# ESP32_EVKIT_v1_0.net
KiCad netlist of a schematic drawn in EAGLE
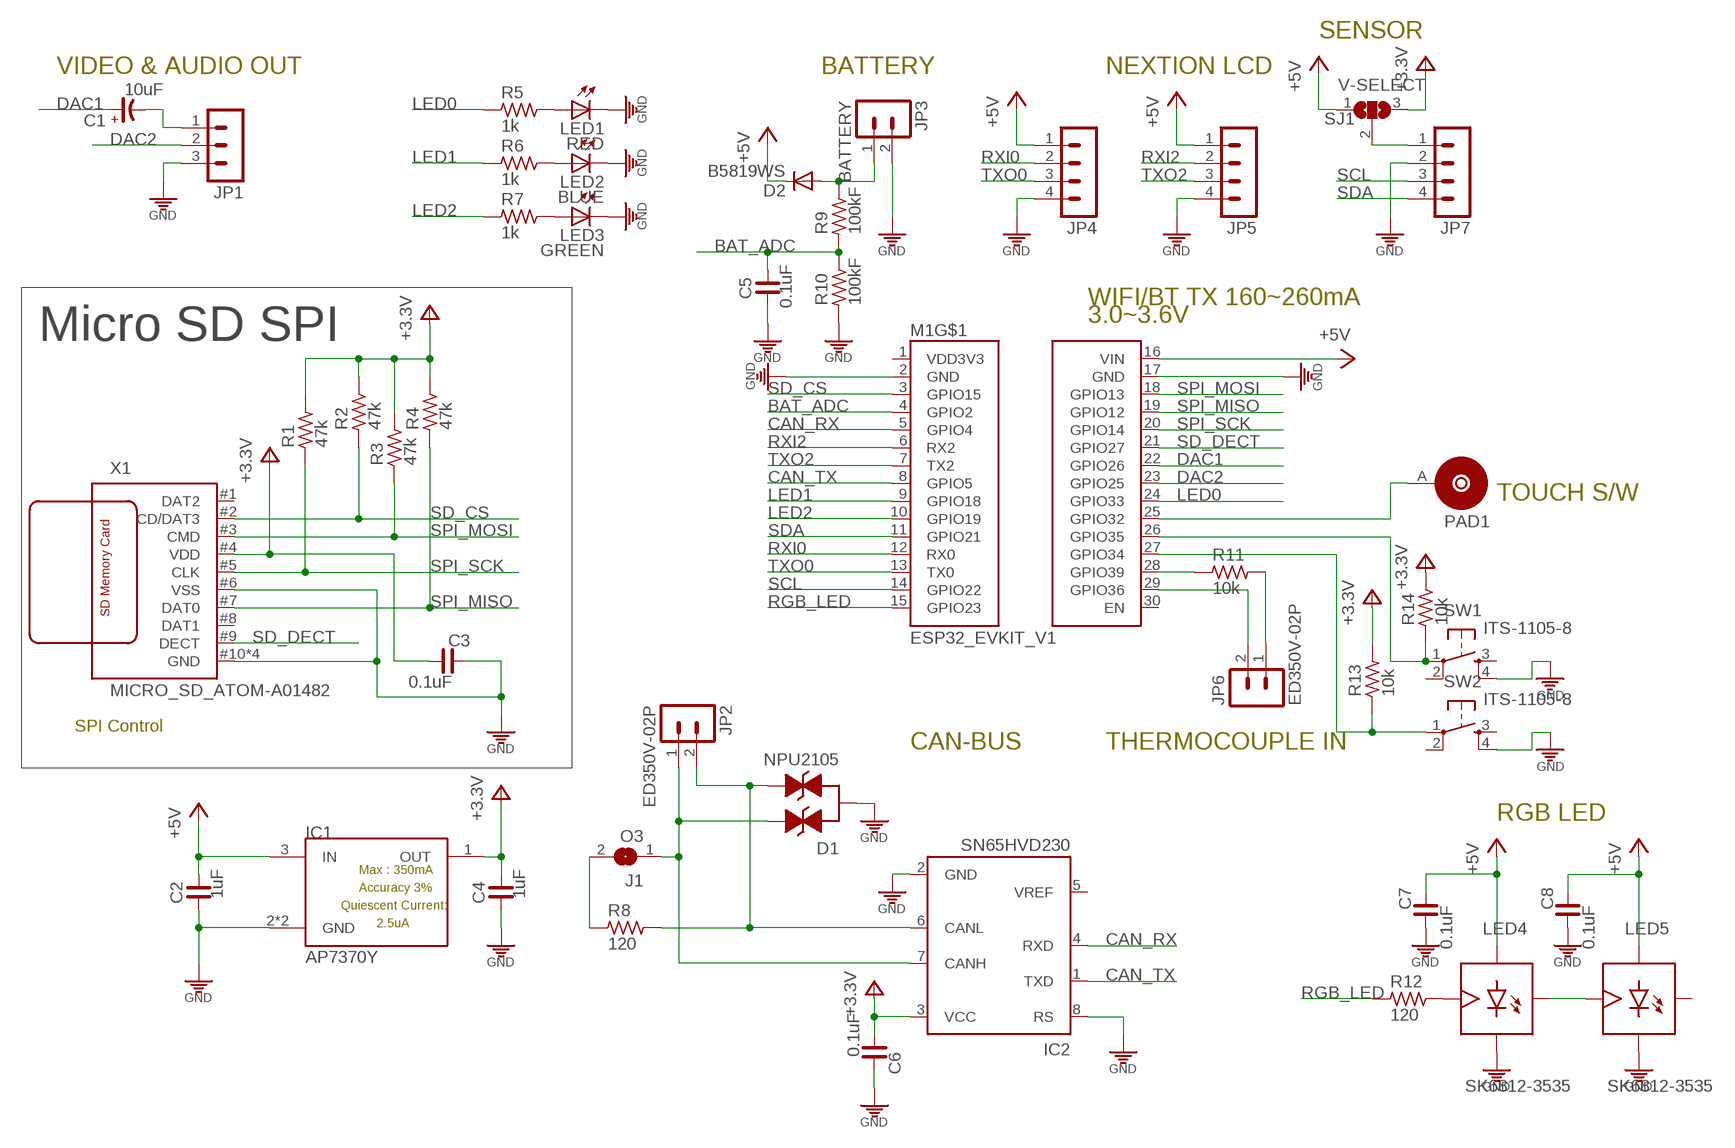
[diagram p0: schematic, sheet 1]

(export (version "E")
  (design (tool "Eeschema 10.0.6"))
  (components
    (comp (ref "C1")
      (value "10uF")
      (footprint "eagle-import:C2012_T")
      (libsource (lib "eagle-import") (part "CP_2012"))
    )
    (comp (ref "C2")
      (value "1uF")
      (footprint "eagle-import:C0603")
      (libsource (lib "eagle-import") (part "C_0603"))
    )
    (comp (ref "C3")
      (value "0.1uF")
      (footprint "eagle-import:C0603")
      (libsource (lib "eagle-import") (part "C_0603"))
    )
    (comp (ref "C4")
      (value "1uF")
      (footprint "eagle-import:C0603")
      (libsource (lib "eagle-import") (part "C_0603"))
    )
    (comp (ref "C5")
      (value "0.1uF")
      (footprint "eagle-import:C0603")
      (libsource (lib "eagle-import") (part "C_0603"))
    )
    (comp (ref "C6")
      (value "0.1uF")
      (footprint "eagle-import:C0603")
      (libsource (lib "eagle-import") (part "C_0603"))
    )
    (comp (ref "C7")
      (value "0.1uF")
      (footprint "eagle-import:C0603")
      (libsource (lib "eagle-import") (part "C_0603"))
    )
    (comp (ref "C8")
      (value "0.1uF")
      (footprint "eagle-import:C0603")
      (libsource (lib "eagle-import") (part "C_0603"))
    )
    (comp (ref "D1")
      (value "NPU2105")
      (footprint "eagle-import:SOT23@2")
      (libsource (lib "eagle-import") (part "NPU2105"))
    )
    (comp (ref "D2")
      (value "B5819WS")
      (footprint "eagle-import:SOD323-W")
      (libsource (lib "eagle-import") (part "B5189WWS"))
    )
    (comp (ref "IC1")
      (value "AP7370Y")
      (footprint "eagle-import:SOT89")
      (libsource (lib "eagle-import") (part "AP7370Y"))
    )
    (comp (ref "IC2")
      (value "SN65HVD230")
      (footprint "eagle-import:SO8")
      (libsource (lib "eagle-import") (part "PCA82C250T"))
    )
    (comp (ref "J1") (value "O3") (footprint "eagle-import:SJ") (libsource (lib "eagle-import") (part "SJ")))
    (comp (ref "JP1")
      (value "MA03-1DEF")
      (footprint "eagle-import:MA03")
      (libsource (lib "eagle-import") (part "MA03-1DEF"))
    )
    (comp (ref "JP2")
      (value "ED350V-02P")
      (footprint "eagle-import:ED350V-02P")
      (libsource (lib "eagle-import") (part "MA02ED350V-02P"))
    )
    (comp (ref "JP3")
      (value "BATTERY")
      (footprint "eagle-import:53398-02")
      (libsource (lib "eagle-import") (part "MA0253398"))
    )
    (comp (ref "JP4")
      (value "MA04-1SMALL")
      (footprint "eagle-import:MA04-1-S")
      (libsource (lib "eagle-import") (part "MA04-1SMALL"))
    )
    (comp (ref "JP5")
      (value "MA04-1SMALL")
      (footprint "eagle-import:MA04-1-S")
      (libsource (lib "eagle-import") (part "MA04-1SMALL"))
    )
    (comp (ref "JP6")
      (value "ED350V-02P")
      (footprint "eagle-import:ED350V-02P")
      (libsource (lib "eagle-import") (part "MA02ED350V-02P"))
    )
    (comp (ref "JP7")
      (value "MA04-1SMALL")
      (footprint "eagle-import:MA04-1-S")
      (libsource (lib "eagle-import") (part "MA04-1SMALL"))
    )
    (comp (ref "LED1")
      (value "RED")
      (footprint "eagle-import:LED-1608")
      (libsource (lib "eagle-import") (part "LEDSMD-1608"))
    )
    (comp (ref "LED2")
      (value "BLUE")
      (footprint "eagle-import:LED-1608")
      (libsource (lib "eagle-import") (part "LEDSMD-1608"))
    )
    (comp (ref "LED3")
      (value "GREEN")
      (footprint "eagle-import:LED-1608")
      (libsource (lib "eagle-import") (part "LEDSMD-1608"))
    )
    (comp (ref "LED4")
      (value "SK6812-3535")
      (footprint "eagle-import:LED3535")
      (libsource (lib "eagle-import") (part "SK68123535"))
    )
    (comp (ref "LED5")
      (value "SK6812-3535")
      (footprint "eagle-import:LED3535")
      (libsource (lib "eagle-import") (part "SK68123535"))
    )
    (comp (ref "M1")
      (value "ESP32_EVKIT_V1")
      (footprint "eagle-import:ESP32_DEVKIT_V1_DOIT")
      (libsource (lib "eagle-import") (part "ESP32_EVKIT_V1"))
    )
    (comp (ref "PAD1")
      (value "TOUCH_PAD01")
      (footprint "eagle-import:TOUCH_PAD1")
      (libsource (lib "eagle-import") (part "TOUCH_PAD01"))
    )
    (comp (ref "R1")
      (value "47k")
      (footprint "eagle-import:R0603")
      (libsource (lib "eagle-import") (part "R_0603"))
    )
    (comp (ref "R2")
      (value "47k")
      (footprint "eagle-import:R0603")
      (libsource (lib "eagle-import") (part "R_0603"))
    )
    (comp (ref "R3")
      (value "47k")
      (footprint "eagle-import:R0603")
      (libsource (lib "eagle-import") (part "R_0603"))
    )
    (comp (ref "R4")
      (value "47k")
      (footprint "eagle-import:R0603")
      (libsource (lib "eagle-import") (part "R_0603"))
    )
    (comp (ref "R5")
      (value "1k")
      (footprint "eagle-import:R0603")
      (libsource (lib "eagle-import") (part "R_0603"))
    )
    (comp (ref "R6")
      (value "1k")
      (footprint "eagle-import:R0603")
      (libsource (lib "eagle-import") (part "R_0603"))
    )
    (comp (ref "R7")
      (value "1k")
      (footprint "eagle-import:R0603")
      (libsource (lib "eagle-import") (part "R_0603"))
    )
    (comp (ref "R8")
      (value "120")
      (footprint "eagle-import:R0603")
      (libsource (lib "eagle-import") (part "R_0603"))
    )
    (comp (ref "R9")
      (value "100kF")
      (footprint "eagle-import:R0603")
      (libsource (lib "eagle-import") (part "R_0603"))
    )
    (comp (ref "R10")
      (value "100kF")
      (footprint "eagle-import:R0603")
      (libsource (lib "eagle-import") (part "R_0603"))
    )
    (comp (ref "R11")
      (value "10k")
      (footprint "eagle-import:R0603")
      (libsource (lib "eagle-import") (part "R_0603"))
    )
    (comp (ref "R12")
      (value "120")
      (footprint "eagle-import:R0603")
      (libsource (lib "eagle-import") (part "R_0603"))
    )
    (comp (ref "R13")
      (value "10k")
      (footprint "eagle-import:R0603")
      (libsource (lib "eagle-import") (part "R_0603"))
    )
    (comp (ref "R14")
      (value "10k")
      (footprint "eagle-import:R0603")
      (libsource (lib "eagle-import") (part "R_0603"))
    )
    (comp (ref "SJ1")
      (value "V-SELECT")
      (footprint "eagle-import:SJ_3")
      (libsource (lib "eagle-import") (part "SOLDERJUMPER_2WAYS"))
    )
    (comp (ref "SW1")
      (value "ITS-1105-8")
      (footprint "eagle-import:ITS-1105")
      (libsource (lib "eagle-import") (part "ITS-1105"))
    )
    (comp (ref "SW2")
      (value "ITS-1105-8")
      (footprint "eagle-import:ITS-1105")
      (libsource (lib "eagle-import") (part "ITS-1105"))
    )
    (comp (ref "X1")
      (value "MICRO_SD_ATOM-A01482")
      (footprint "eagle-import:ATOM-A01482")
      (libsource (lib "eagle-import") (part "MICRO_SD_ATOM-A01482"))
    )
  )
  (nets
    (net (code "1") (name "+3V3") (class "Default")
      (node (ref "C3") (pin "2") (pinfunction "2_2") (pintype "passive"))
      (node (ref "C4") (pin "1") (pinfunction "1_1") (pintype "passive"))
      (node (ref "C6") (pin "2") (pinfunction "2_2") (pintype "passive"))
      (node (ref "IC1") (pin "1") (pinfunction "OUT_1") (pintype "power_in"))
      (node (ref "IC2") (pin "3") (pinfunction "VCC_3") (pintype "power_in"))
      (node (ref "R1") (pin "2") (pinfunction "2_2") (pintype "passive"))
      (node (ref "R13") (pin "2") (pinfunction "2_2") (pintype "passive"))
      (node (ref "R14") (pin "2") (pinfunction "2_2") (pintype "passive"))
      (node (ref "R2") (pin "2") (pinfunction "2_2") (pintype "passive"))
      (node (ref "R3") (pin "2") (pinfunction "2_2") (pintype "passive"))
      (node (ref "R4") (pin "2") (pinfunction "2_2") (pintype "passive"))
      (node (ref "SJ1") (pin "3") (pinfunction "3_3") (pintype "passive"))
      (node (ref "X1") (pin "#4") (pinfunction "VDD_#4") (pintype "passive"))
    )
    (net (code "2") (name "+5V") (class "Default")
      (node (ref "C2") (pin "1") (pinfunction "1_1") (pintype "passive"))
      (node (ref "C7") (pin "1") (pinfunction "1_1") (pintype "passive"))
      (node (ref "C8") (pin "1") (pinfunction "1_1") (pintype "passive"))
      (node (ref "D2") (pin "C") (pinfunction "C_C") (pintype "passive"))
      (node (ref "IC1") (pin "3") (pinfunction "IN_3") (pintype "power_in"))
      (node (ref "JP4") (pin "1") (pinfunction "1_1") (pintype "passive"))
      (node (ref "JP5") (pin "1") (pinfunction "1_1") (pintype "passive"))
      (node (ref "LED4") (pin "4") (pinfunction "VDD_4") (pintype "power_in"))
      (node (ref "LED5") (pin "4") (pinfunction "VDD_4") (pintype "power_in"))
      (node (ref "M1") (pin "16") (pinfunction "VIN_16") (pintype "power_in"))
      (node (ref "SJ1") (pin "1") (pinfunction "1_1") (pintype "passive"))
    )
    (net (code "3") (name "/BAT_ADC") (class "Default")
      (node (ref "C5") (pin "1") (pinfunction "1_1") (pintype "passive"))
      (node (ref "M1") (pin "4") (pinfunction "GPIO2_4") (pintype "bidirectional"))
      (node (ref "R10") (pin "2") (pinfunction "2_2") (pintype "passive"))
      (node (ref "R9") (pin "1") (pinfunction "1_1") (pintype "passive"))
    )
    (net (code "4") (name "/CAN_RX") (class "Default")
      (node (ref "IC2") (pin "4") (pinfunction "RXD_4") (pintype "output"))
      (node (ref "M1") (pin "5") (pinfunction "GPIO4_5") (pintype "bidirectional"))
    )
    (net (code "5") (name "/CAN_TX") (class "Default")
      (node (ref "IC2") (pin "1") (pinfunction "TXD_1") (pintype "input"))
      (node (ref "M1") (pin "8") (pinfunction "GPIO5_8") (pintype "bidirectional"))
    )
    (net (code "6") (name "/DAC1") (class "Default")
      (node (ref "C1") (pin "+") (pinfunction "+_+") (pintype "passive"))
      (node (ref "M1") (pin "22") (pinfunction "GPIO26_22") (pintype "bidirectional"))
    )
    (net (code "7") (name "/DAC2") (class "Default")
      (node (ref "JP1") (pin "2") (pinfunction "2_2") (pintype "passive"))
      (node (ref "M1") (pin "23") (pinfunction "GPIO25_23") (pintype "bidirectional"))
    )
    (net (code "8") (name "/LED0") (class "Default")
      (node (ref "M1") (pin "24") (pinfunction "GPIO33_24") (pintype "bidirectional"))
      (node (ref "R5") (pin "1") (pinfunction "1_1") (pintype "passive"))
    )
    (net (code "9") (name "/LED1") (class "Default")
      (node (ref "M1") (pin "9") (pinfunction "GPIO18_9") (pintype "bidirectional"))
      (node (ref "R6") (pin "1") (pinfunction "1_1") (pintype "passive"))
    )
    (net (code "10") (name "/LED2") (class "Default")
      (node (ref "M1") (pin "10") (pinfunction "GPIO19_10") (pintype "bidirectional"))
      (node (ref "R7") (pin "1") (pinfunction "1_1") (pintype "passive"))
    )
    (net (code "11") (name "/RGB_LED") (class "Default")
      (node (ref "M1") (pin "15") (pinfunction "GPIO23_15") (pintype "bidirectional"))
      (node (ref "R12") (pin "1") (pinfunction "1_1") (pintype "passive"))
    )
    (net (code "12") (name "/RXI0") (class "Default")
      (node (ref "JP4") (pin "2") (pinfunction "2_2") (pintype "passive"))
      (node (ref "M1") (pin "12") (pinfunction "RX0_12") (pintype "bidirectional"))
    )
    (net (code "13") (name "/RXI2") (class "Default")
      (node (ref "JP5") (pin "2") (pinfunction "2_2") (pintype "passive"))
      (node (ref "M1") (pin "6") (pinfunction "RX2_6") (pintype "bidirectional"))
    )
    (net (code "14") (name "/SCL") (class "Default")
      (node (ref "JP7") (pin "3") (pinfunction "3_3") (pintype "passive"))
      (node (ref "M1") (pin "14") (pinfunction "GPIO22_14") (pintype "bidirectional"))
    )
    (net (code "15") (name "/SDA") (class "Default")
      (node (ref "JP7") (pin "4") (pinfunction "4_4") (pintype "passive"))
      (node (ref "M1") (pin "11") (pinfunction "GPIO21_11") (pintype "bidirectional"))
    )
    (net (code "16") (name "/SD_CS") (class "Default")
      (node (ref "M1") (pin "3") (pinfunction "GPIO15_3") (pintype "bidirectional"))
      (node (ref "R2") (pin "1") (pinfunction "1_1") (pintype "passive"))
      (node (ref "X1") (pin "#2") (pinfunction "CD/DAT3_#2") (pintype "passive"))
    )
    (net (code "17") (name "/SD_DECT") (class "Default")
      (node (ref "M1") (pin "21") (pinfunction "GPIO27_21") (pintype "bidirectional"))
      (node (ref "X1") (pin "#9") (pinfunction "DECT_#9") (pintype "passive"))
    )
    (net (code "18") (name "/SPI_MISO") (class "Default")
      (node (ref "M1") (pin "19") (pinfunction "GPIO12_19") (pintype "bidirectional"))
      (node (ref "R4") (pin "1") (pinfunction "1_1") (pintype "passive"))
      (node (ref "X1") (pin "#7") (pinfunction "DAT0_#7") (pintype "passive"))
    )
    (net (code "19") (name "/SPI_MOSI") (class "Default")
      (node (ref "M1") (pin "18") (pinfunction "GPIO13_18") (pintype "bidirectional"))
      (node (ref "R3") (pin "1") (pinfunction "1_1") (pintype "passive"))
      (node (ref "X1") (pin "#3") (pinfunction "CMD_#3") (pintype "passive"))
    )
    (net (code "20") (name "/SPI_SCK") (class "Default")
      (node (ref "M1") (pin "20") (pinfunction "GPIO14_20") (pintype "bidirectional"))
      (node (ref "R1") (pin "1") (pinfunction "1_1") (pintype "passive"))
      (node (ref "X1") (pin "#5") (pinfunction "CLK_#5") (pintype "passive"))
    )
    (net (code "21") (name "/TXO0") (class "Default")
      (node (ref "JP4") (pin "3") (pinfunction "3_3") (pintype "passive"))
      (node (ref "M1") (pin "13") (pinfunction "TX0_13") (pintype "bidirectional"))
    )
    (net (code "22") (name "/TXO2") (class "Default")
      (node (ref "JP5") (pin "3") (pinfunction "3_3") (pintype "passive"))
      (node (ref "M1") (pin "7") (pinfunction "TX2_7") (pintype "bidirectional"))
    )
    (net (code "23") (name "/VDD3V3") (class "Default")
      (node (ref "M1") (pin "1") (pinfunction "VDD3V3_1") (pintype "power_in"))
    )
    (net (code "24") (name "GND") (class "Default")
      (node (ref "C2") (pin "2") (pinfunction "2_2") (pintype "passive"))
      (node (ref "C3") (pin "1") (pinfunction "1_1") (pintype "passive"))
      (node (ref "C4") (pin "2") (pinfunction "2_2") (pintype "passive"))
      (node (ref "C5") (pin "2") (pinfunction "2_2") (pintype "passive"))
      (node (ref "C6") (pin "1") (pinfunction "1_1") (pintype "passive"))
      (node (ref "C7") (pin "2") (pinfunction "2_2") (pintype "passive"))
      (node (ref "C8") (pin "2") (pinfunction "2_2") (pintype "passive"))
      (node (ref "D1") (pin "D") (pinfunction "PIN3_D") (pintype "passive"))
      (node (ref "IC1") (pin "2") (pinfunction "GND_2") (pintype "power_in"))
      (node (ref "IC1") (pin "2@1") (pinfunction "GND_2@1") (pintype "power_in"))
      (node (ref "IC2") (pin "2") (pinfunction "GND_2") (pintype "power_in"))
      (node (ref "IC2") (pin "8") (pinfunction "RS_8") (pintype "input"))
      (node (ref "JP1") (pin "3") (pinfunction "3_3") (pintype "passive"))
      (node (ref "JP3") (pin "2") (pinfunction "2_2") (pintype "passive"))
      (node (ref "JP4") (pin "4") (pinfunction "4_4") (pintype "passive"))
      (node (ref "JP5") (pin "4") (pinfunction "4_4") (pintype "passive"))
      (node (ref "JP7") (pin "2") (pinfunction "2_2") (pintype "passive"))
      (node (ref "LED1") (pin "C") (pinfunction "C_C") (pintype "passive"))
      (node (ref "LED2") (pin "C") (pinfunction "C_C") (pintype "passive"))
      (node (ref "LED3") (pin "C") (pinfunction "C_C") (pintype "passive"))
      (node (ref "LED4") (pin "2") (pinfunction "VSS_2") (pintype "power_in"))
      (node (ref "LED5") (pin "2") (pinfunction "VSS_2") (pintype "power_in"))
      (node (ref "M1") (pin "17") (pinfunction "GND_17") (pintype "power_in"))
      (node (ref "M1") (pin "2") (pinfunction "GND_2") (pintype "power_in"))
      (node (ref "R10") (pin "1") (pinfunction "1_1") (pintype "passive"))
      (node (ref "SW1") (pin "4") (pinfunction "4_4") (pintype "passive"))
      (node (ref "SW2") (pin "4") (pinfunction "4_4") (pintype "passive"))
      (node (ref "X1") (pin "#10") (pinfunction "GND_#10") (pintype "passive"))
      (node (ref "X1") (pin "#10@") (pinfunction "GND_#10@") (pintype "passive"))
      (node (ref "X1") (pin "#10@1") (pinfunction "GND_#10@1") (pintype "passive"))
      (node (ref "X1") (pin "#13") (pinfunction "GND_#13") (pintype "passive"))
      (node (ref "X1") (pin "#6") (pinfunction "VSS_#6") (pintype "passive"))
    )
    (net (code "25") (name "Net-(C1-Pad-)") (class "Default")
      (node (ref "C1") (pin "-") (pinfunction "-_-") (pintype "passive"))
      (node (ref "JP1") (pin "1") (pinfunction "1_1") (pintype "passive"))
    )
    (net (code "26") (name "Net-(D1-PIN1)") (class "Default")
      (node (ref "D1") (pin "G") (pinfunction "PIN1_G") (pintype "passive"))
      (node (ref "IC2") (pin "7") (pinfunction "CANH_7") (pintype "bidirectional"))
      (node (ref "J1") (pin "1") (pinfunction "1_1") (pintype "passive"))
      (node (ref "JP2") (pin "1") (pinfunction "1_1") (pintype "passive"))
    )
    (net (code "27") (name "Net-(D1-PIN2)") (class "Default")
      (node (ref "D1") (pin "S") (pinfunction "PIN2_S") (pintype "passive"))
      (node (ref "IC2") (pin "6") (pinfunction "CANL_6") (pintype "bidirectional"))
      (node (ref "JP2") (pin "2") (pinfunction "2_2") (pintype "passive"))
      (node (ref "R8") (pin "2") (pinfunction "2_2") (pintype "passive"))
    )
    (net (code "28") (name "Net-(D2-PadA)") (class "Default")
      (node (ref "D2") (pin "A") (pinfunction "A_A") (pintype "passive"))
      (node (ref "JP3") (pin "1") (pinfunction "1_1") (pintype "passive"))
      (node (ref "R9") (pin "2") (pinfunction "2_2") (pintype "passive"))
    )
    (net (code "29") (name "Net-(J1-Pad2)") (class "Default")
      (node (ref "J1") (pin "2") (pinfunction "2_2") (pintype "passive"))
      (node (ref "R8") (pin "1") (pinfunction "1_1") (pintype "passive"))
    )
    (net (code "30") (name "Net-(JP6-Pad1)") (class "Default")
      (node (ref "JP6") (pin "1") (pinfunction "1_1") (pintype "passive"))
      (node (ref "R11") (pin "2") (pinfunction "2_2") (pintype "passive"))
    )
    (net (code "31") (name "Net-(JP7-Pad1)") (class "Default")
      (node (ref "JP7") (pin "1") (pinfunction "1_1") (pintype "passive"))
      (node (ref "SJ1") (pin "2") (pinfunction "2_2") (pintype "passive"))
    )
    (net (code "32") (name "Net-(LED1-PadA)") (class "Default")
      (node (ref "LED1") (pin "A") (pinfunction "A_A") (pintype "passive"))
      (node (ref "R5") (pin "2") (pinfunction "2_2") (pintype "passive"))
    )
    (net (code "33") (name "Net-(LED2-PadA)") (class "Default")
      (node (ref "LED2") (pin "A") (pinfunction "A_A") (pintype "passive"))
      (node (ref "R6") (pin "2") (pinfunction "2_2") (pintype "passive"))
    )
    (net (code "34") (name "Net-(LED3-PadA)") (class "Default")
      (node (ref "LED3") (pin "A") (pinfunction "A_A") (pintype "passive"))
      (node (ref "R7") (pin "2") (pinfunction "2_2") (pintype "passive"))
    )
    (net (code "35") (name "Net-(LED4-DIN)") (class "Default")
      (node (ref "LED4") (pin "3") (pinfunction "DIN_3") (pintype "input"))
      (node (ref "R12") (pin "2") (pinfunction "2_2") (pintype "passive"))
    )
    (net (code "36") (name "Net-(LED4-DOUT)") (class "Default")
      (node (ref "LED4") (pin "1") (pinfunction "DOUT_1") (pintype "output"))
      (node (ref "LED5") (pin "3") (pinfunction "DIN_3") (pintype "input"))
    )
    (net (code "37") (name "Net-(M1B-GPIO32)") (class "Default")
      (node (ref "M1") (pin "25") (pinfunction "GPIO32_25") (pintype "bidirectional"))
      (node (ref "PAD1") (pin "A") (pinfunction "2_A") (pintype "passive"))
    )
    (net (code "38") (name "Net-(M1B-GPIO34)") (class "Default")
      (node (ref "M1") (pin "27") (pinfunction "GPIO34_27") (pintype "input"))
      (node (ref "R13") (pin "1") (pinfunction "1_1") (pintype "passive"))
      (node (ref "SW2") (pin "1") (pinfunction "1_1") (pintype "passive"))
    )
    (net (code "39") (name "Net-(M1B-GPIO35)") (class "Default")
      (node (ref "M1") (pin "26") (pinfunction "GPIO35_26") (pintype "input"))
      (node (ref "R14") (pin "1") (pinfunction "1_1") (pintype "passive"))
      (node (ref "SW1") (pin "1") (pinfunction "1_1") (pintype "passive"))
    )
    (net (code "40") (name "Net-(M1B-GPIO36)") (class "Default")
      (node (ref "JP6") (pin "2") (pinfunction "2_2") (pintype "passive"))
      (node (ref "M1") (pin "29") (pinfunction "GPIO36_29") (pintype "input"))
    )
    (net (code "41") (name "Net-(M1B-GPIO39)") (class "Default")
      (node (ref "M1") (pin "28") (pinfunction "GPIO39_28") (pintype "input"))
      (node (ref "R11") (pin "1") (pinfunction "1_1") (pintype "passive"))
    )
    (net (code "42") (name "unconnected-(IC2-VREF-Pad5)") (class "Default")
      (node (ref "IC2") (pin "5") (pinfunction "VREF_5") (pintype "output"))
    )
    (net (code "43") (name "unconnected-(LED5-DOUT-Pad1)") (class "Default")
      (node (ref "LED5") (pin "1") (pinfunction "DOUT_1") (pintype "output"))
    )
    (net (code "44") (name "unconnected-(M1B-EN-Pad30)") (class "Default")
      (node (ref "M1") (pin "30") (pinfunction "EN_30") (pintype "input"))
    )
    (net (code "45") (name "unconnected-(SW1-Pad2)") (class "Default")
      (node (ref "SW1") (pin "2") (pinfunction "2_2") (pintype "passive"))
    )
    (net (code "46") (name "unconnected-(SW1-Pad3)") (class "Default")
      (node (ref "SW1") (pin "3") (pinfunction "3_3") (pintype "passive"))
    )
    (net (code "47") (name "unconnected-(SW2-Pad2)") (class "Default")
      (node (ref "SW2") (pin "2") (pinfunction "2_2") (pintype "passive"))
    )
    (net (code "48") (name "unconnected-(SW2-Pad3)") (class "Default")
      (node (ref "SW2") (pin "3") (pinfunction "3_3") (pintype "passive"))
    )
    (net (code "49") (name "unconnected-(X1-DAT1-Pad#8)") (class "Default")
      (node (ref "X1") (pin "#8") (pinfunction "DAT1_#8") (pintype "passive"))
    )
    (net (code "50") (name "unconnected-(X1-DAT2-Pad#1)") (class "Default")
      (node (ref "X1") (pin "#1") (pinfunction "DAT2_#1") (pintype "passive"))
    )
  )
)
